# PCB-MicroAudio.net
KiCad netlist of a schematic drawn in EAGLE
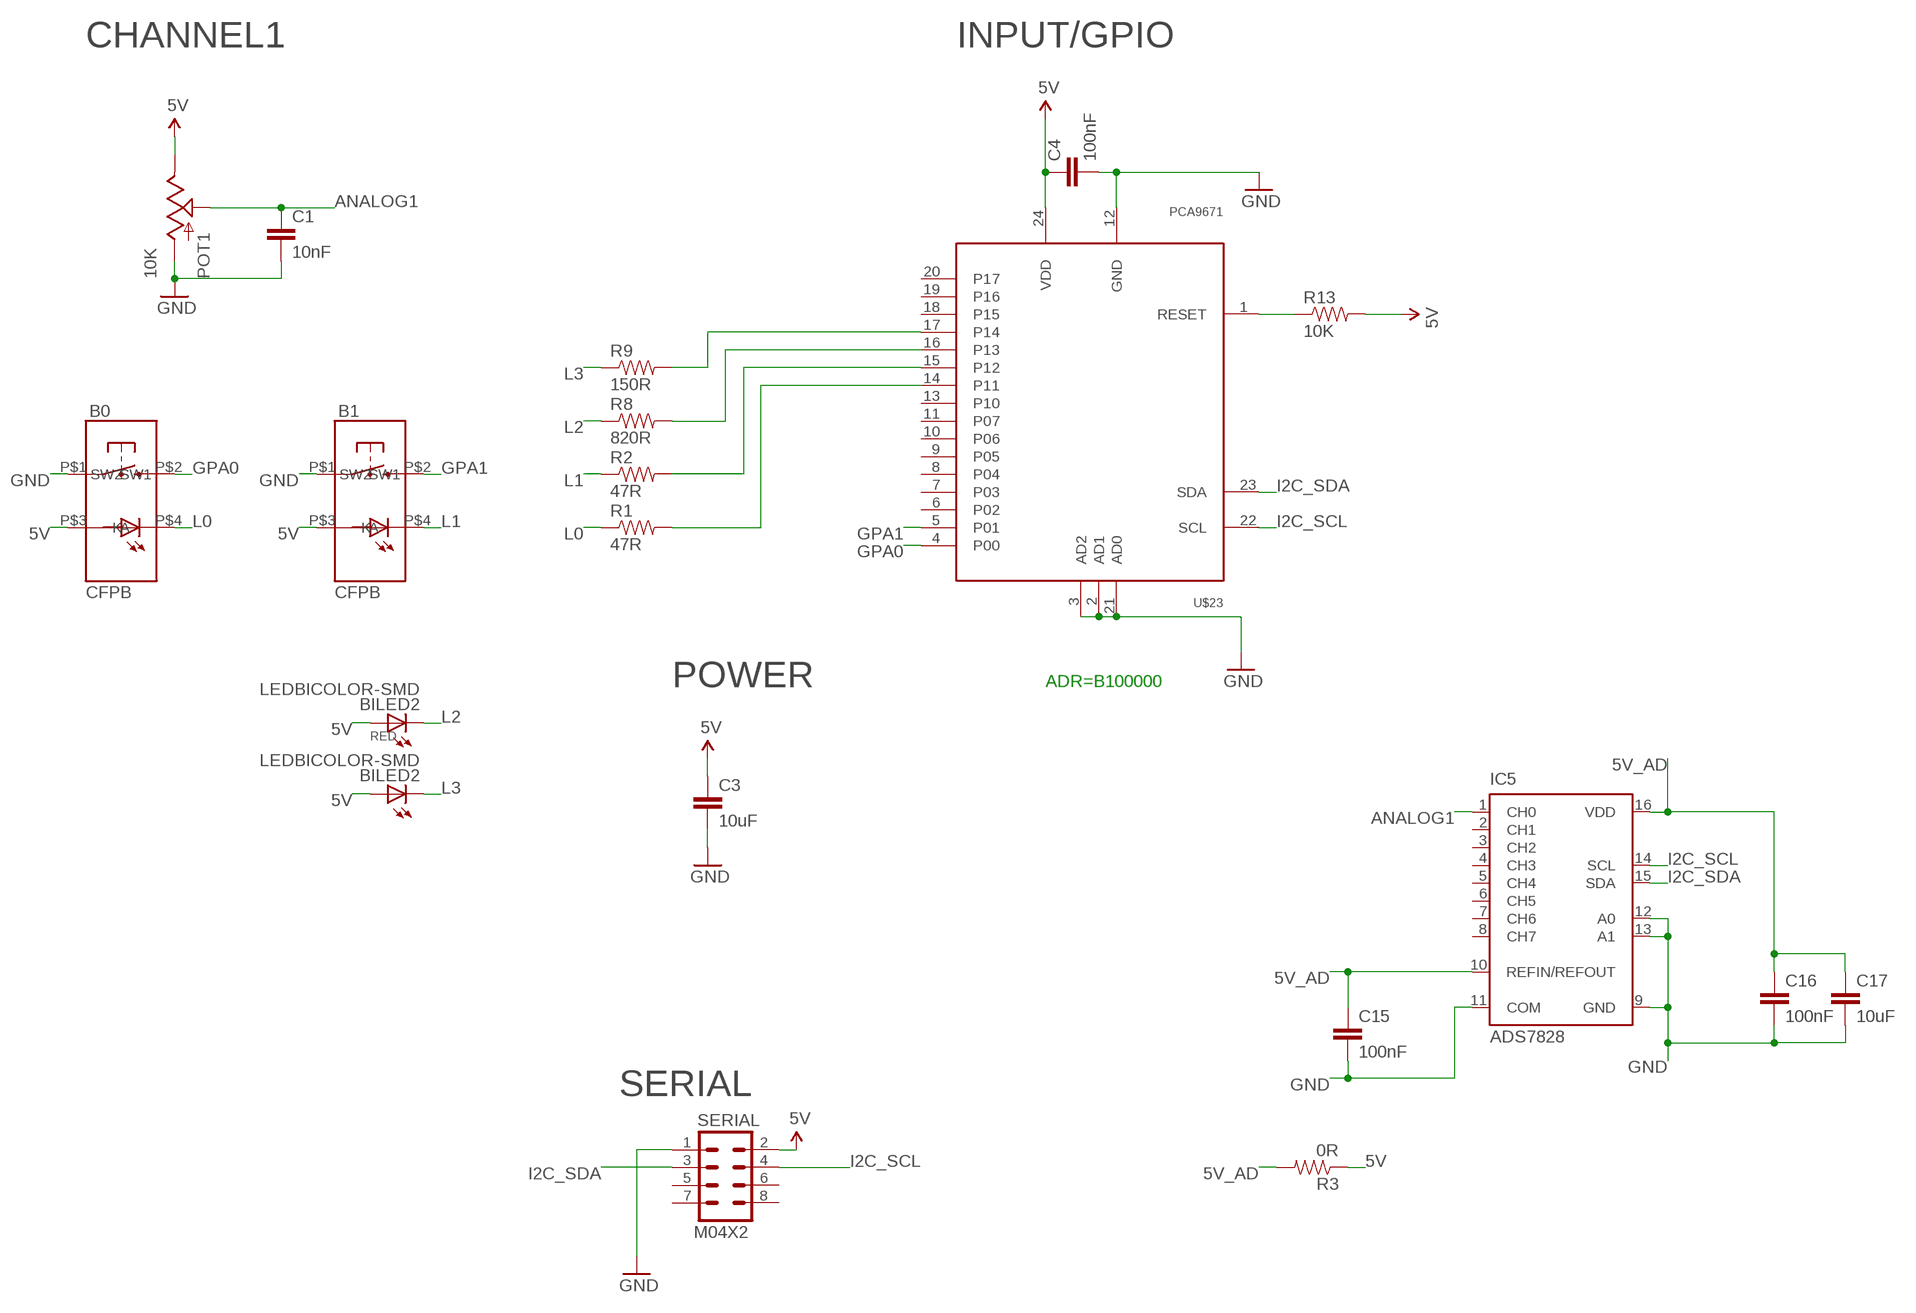
[diagram p0: schematic, sheet 1]

(export (version "E")
  (design (tool "Eeschema 10.0.6"))
  (components
    (comp (ref "B0")
      (value "CFPB")
      (footprint "eagle-import:CFPB-6_9MM")
      (libsource (lib "eagle-import") (part "CFPB"))
    )
    (comp (ref "B1")
      (value "CFPB")
      (footprint "eagle-import:CFPB-6_9MM")
      (libsource (lib "eagle-import") (part "CFPB"))
    )
    (comp (ref "BILED2")
      (value "LEDBICOLOR-SMD")
      (footprint "eagle-import:LEDBICOLOR-SMD")
      (libsource (lib "eagle-import") (part "LEDBICOLOR-SMD"))
    )
    (comp (ref "C1")
      (value "10nF")
      (footprint "eagle-import:0603-CAP")
      (libsource (lib "eagle-import") (part "CAP0603-CAP"))
    )
    (comp (ref "C3")
      (value "10uF")
      (footprint "eagle-import:0805")
      (libsource (lib "eagle-import") (part "CAP0805"))
    )
    (comp (ref "C4")
      (value "100nF")
      (footprint "eagle-import:0603-CAP")
      (libsource (lib "eagle-import") (part "CAP0603-CAP"))
    )
    (comp (ref "C15")
      (value "100nF")
      (footprint "eagle-import:0603-CAP")
      (libsource (lib "eagle-import") (part "CAP0603-CAP"))
    )
    (comp (ref "C16")
      (value "100nF")
      (footprint "eagle-import:0603-CAP")
      (libsource (lib "eagle-import") (part "CAP0603-CAP"))
    )
    (comp (ref "C17")
      (value "10uF")
      (footprint "eagle-import:0805")
      (libsource (lib "eagle-import") (part "CAP0805"))
    )
    (comp (ref "IC5")
      (value "ADS7828")
      (footprint "eagle-import:TSSOP16-PW")
      (fields (field (name "MF") "TEXAS INSTRUMENTS") (field (name "MPN") "ADS7828E/250"))
      (libsource (lib "eagle-import") (part "ADS7828"))
    )
    (comp (ref "POT1")
      (value "10K")
      (footprint "eagle-import:ALPS_POT")
      (libsource (lib "eagle-import") (part "POT"))
    )
    (comp (ref "R1")
      (value "47R")
      (footprint "eagle-import:0603-RES")
      (libsource (lib "eagle-import") (part "RESISTOR0603-RES"))
    )
    (comp (ref "R2")
      (value "47R")
      (footprint "eagle-import:0603-RES")
      (libsource (lib "eagle-import") (part "RESISTOR0603-RES"))
    )
    (comp (ref "R3")
      (value "0R")
      (footprint "eagle-import:0603-RES")
      (libsource (lib "eagle-import") (part "RESISTOR0603-RES"))
    )
    (comp (ref "R8")
      (value "820R")
      (footprint "eagle-import:0603-RES")
      (libsource (lib "eagle-import") (part "RESISTOR0603-RES"))
    )
    (comp (ref "R9")
      (value "150R")
      (footprint "eagle-import:0603-RES")
      (libsource (lib "eagle-import") (part "RESISTOR0603-RES"))
    )
    (comp (ref "R13")
      (value "10K")
      (footprint "eagle-import:0603-RES")
      (libsource (lib "eagle-import") (part "RESISTOR0603-RES"))
    )
    (comp (ref "SERIAL")
      (value "M04X2")
      (footprint "eagle-import:2X4")
      (libsource (lib "eagle-import") (part "M04X2"))
    )
    (comp (ref "U$23")
      (value "PCA9671")
      (footprint "eagle-import:TSSOP24")
      (libsource (lib "eagle-import") (part "PCA9671"))
    )
  )
  (nets
    (net (code "1") (name "5V") (class "Default")
      (node (ref "B0") (pin "P$3") (pinfunction "A_P$3") (pintype "bidirectional"))
      (node (ref "B1") (pin "P$3") (pinfunction "A_P$3") (pintype "bidirectional"))
      (node (ref "BILED2") (pin "P$1") (pinfunction "A_P$1") (pintype "passive"))
      (node (ref "BILED2") (pin "P$3") (pinfunction "A1_P$3") (pintype "passive"))
      (node (ref "C3") (pin "1") (pinfunction "1_1") (pintype "passive"))
      (node (ref "C4") (pin "1") (pinfunction "1_1") (pintype "passive"))
      (node (ref "POT1") (pin "P$1") (pinfunction "E_P$1") (pintype "passive"))
      (node (ref "R13") (pin "2") (pinfunction "2_2") (pintype "passive"))
      (node (ref "R3") (pin "1") (pinfunction "1_1") (pintype "passive"))
      (node (ref "SERIAL") (pin "2") (pinfunction "2_2") (pintype "passive"))
      (node (ref "U$23") (pin "24") (pinfunction "VDD_24") (pintype "power_in"))
    )
    (net (code "2") (name "5V_AD") (class "Default")
      (node (ref "C15") (pin "1") (pinfunction "1_1") (pintype "passive"))
      (node (ref "C16") (pin "1") (pinfunction "1_1") (pintype "passive"))
      (node (ref "C17") (pin "1") (pinfunction "1_1") (pintype "passive"))
      (node (ref "IC5") (pin "10") (pinfunction "REFIN/REFOUT_10") (pintype "passive"))
      (node (ref "IC5") (pin "16") (pinfunction "VDD_16") (pintype "power_in"))
      (node (ref "R3") (pin "2") (pinfunction "2_2") (pintype "passive"))
    )
    (net (code "3") (name "ANALOG1") (class "Default")
      (node (ref "C1") (pin "1") (pinfunction "1_1") (pintype "passive"))
      (node (ref "IC5") (pin "1") (pinfunction "CH0_1") (pintype "input"))
      (node (ref "POT1") (pin "P$2") (pinfunction "S_P$2") (pintype "passive"))
    )
    (net (code "4") (name "GND") (class "Default")
      (node (ref "B0") (pin "P$1") (pinfunction "SW1_P$1") (pintype "bidirectional"))
      (node (ref "B1") (pin "P$1") (pinfunction "SW1_P$1") (pintype "bidirectional"))
      (node (ref "C1") (pin "2") (pinfunction "2_2") (pintype "passive"))
      (node (ref "C15") (pin "2") (pinfunction "2_2") (pintype "passive"))
      (node (ref "C16") (pin "2") (pinfunction "2_2") (pintype "passive"))
      (node (ref "C17") (pin "2") (pinfunction "2_2") (pintype "passive"))
      (node (ref "C3") (pin "2") (pinfunction "2_2") (pintype "passive"))
      (node (ref "C4") (pin "2") (pinfunction "2_2") (pintype "passive"))
      (node (ref "IC5") (pin "11") (pinfunction "COM_11") (pintype "input"))
      (node (ref "IC5") (pin "12") (pinfunction "A0_12") (pintype "input"))
      (node (ref "IC5") (pin "13") (pinfunction "A1_13") (pintype "input"))
      (node (ref "IC5") (pin "9") (pinfunction "GND_9") (pintype "power_in"))
      (node (ref "POT1") (pin "P$3") (pinfunction "A_P$3") (pintype "passive"))
      (node (ref "SERIAL") (pin "1") (pinfunction "1_1") (pintype "passive"))
      (node (ref "U$23") (pin "12") (pinfunction "GND_12") (pintype "power_in"))
      (node (ref "U$23") (pin "2") (pinfunction "AD1_2") (pintype "input"))
      (node (ref "U$23") (pin "21") (pinfunction "AD0_21") (pintype "input"))
      (node (ref "U$23") (pin "3") (pinfunction "AD2_3") (pintype "input"))
    )
    (net (code "5") (name "GPA0") (class "Default")
      (node (ref "B0") (pin "P$2") (pinfunction "SW2_P$2") (pintype "bidirectional"))
      (node (ref "U$23") (pin "4") (pinfunction "P00_4") (pintype "output"))
    )
    (net (code "6") (name "GPA1") (class "Default")
      (node (ref "B1") (pin "P$2") (pinfunction "SW2_P$2") (pintype "bidirectional"))
      (node (ref "U$23") (pin "5") (pinfunction "P01_5") (pintype "output"))
    )
    (net (code "7") (name "I2C_SCL") (class "Default")
      (node (ref "IC5") (pin "14") (pinfunction "SCL_14") (pintype "input"))
      (node (ref "SERIAL") (pin "4") (pinfunction "4_4") (pintype "passive"))
      (node (ref "U$23") (pin "22") (pinfunction "SCL_22") (pintype "input"))
    )
    (net (code "8") (name "I2C_SDA") (class "Default")
      (node (ref "IC5") (pin "15") (pinfunction "SDA_15") (pintype "bidirectional"))
      (node (ref "SERIAL") (pin "3") (pinfunction "3_3") (pintype "passive"))
      (node (ref "U$23") (pin "23") (pinfunction "SDA_23") (pintype "input"))
    )
    (net (code "9") (name "L0") (class "Default")
      (node (ref "B0") (pin "P$4") (pinfunction "K_P$4") (pintype "bidirectional"))
      (node (ref "R1") (pin "1") (pinfunction "1_1") (pintype "passive"))
    )
    (net (code "10") (name "L1") (class "Default")
      (node (ref "B1") (pin "P$4") (pinfunction "K_P$4") (pintype "bidirectional"))
      (node (ref "R2") (pin "1") (pinfunction "1_1") (pintype "passive"))
    )
    (net (code "11") (name "L2") (class "Default")
      (node (ref "BILED2") (pin "P$2") (pinfunction "C_P$2") (pintype "passive"))
      (node (ref "R8") (pin "1") (pinfunction "1_1") (pintype "passive"))
    )
    (net (code "12") (name "L3") (class "Default")
      (node (ref "BILED2") (pin "P$4") (pinfunction "C1_P$4") (pintype "passive"))
      (node (ref "R9") (pin "1") (pinfunction "1_1") (pintype "passive"))
    )
    (net (code "13") (name "Net-(U$23-P11)") (class "Default")
      (node (ref "R1") (pin "2") (pinfunction "2_2") (pintype "passive"))
      (node (ref "U$23") (pin "14") (pinfunction "P11_14") (pintype "output"))
    )
    (net (code "14") (name "Net-(U$23-P12)") (class "Default")
      (node (ref "R2") (pin "2") (pinfunction "2_2") (pintype "passive"))
      (node (ref "U$23") (pin "15") (pinfunction "P12_15") (pintype "output"))
    )
    (net (code "15") (name "Net-(U$23-P13)") (class "Default")
      (node (ref "R8") (pin "2") (pinfunction "2_2") (pintype "passive"))
      (node (ref "U$23") (pin "16") (pinfunction "P13_16") (pintype "output"))
    )
    (net (code "16") (name "Net-(U$23-P14)") (class "Default")
      (node (ref "R9") (pin "2") (pinfunction "2_2") (pintype "passive"))
      (node (ref "U$23") (pin "17") (pinfunction "P14_17") (pintype "output"))
    )
    (net (code "17") (name "Net-(U$23-RESET)") (class "Default")
      (node (ref "R13") (pin "1") (pinfunction "1_1") (pintype "passive"))
      (node (ref "U$23") (pin "1") (pinfunction "RESET_1") (pintype "input"))
    )
    (net (code "18") (name "unconnected-(IC5-CH1-Pad2)") (class "Default")
      (node (ref "IC5") (pin "2") (pinfunction "CH1_2") (pintype "input"))
    )
    (net (code "19") (name "unconnected-(IC5-CH2-Pad3)") (class "Default")
      (node (ref "IC5") (pin "3") (pinfunction "CH2_3") (pintype "input"))
    )
    (net (code "20") (name "unconnected-(IC5-CH3-Pad4)") (class "Default")
      (node (ref "IC5") (pin "4") (pinfunction "CH3_4") (pintype "input"))
    )
    (net (code "21") (name "unconnected-(IC5-CH4-Pad5)") (class "Default")
      (node (ref "IC5") (pin "5") (pinfunction "CH4_5") (pintype "input"))
    )
    (net (code "22") (name "unconnected-(IC5-CH5-Pad6)") (class "Default")
      (node (ref "IC5") (pin "6") (pinfunction "CH5_6") (pintype "input"))
    )
    (net (code "23") (name "unconnected-(IC5-CH6-Pad7)") (class "Default")
      (node (ref "IC5") (pin "7") (pinfunction "CH6_7") (pintype "input"))
    )
    (net (code "24") (name "unconnected-(IC5-CH7-Pad8)") (class "Default")
      (node (ref "IC5") (pin "8") (pinfunction "CH7_8") (pintype "input"))
    )
    (net (code "25") (name "unconnected-(SERIAL-Pad5)") (class "Default")
      (node (ref "SERIAL") (pin "5") (pinfunction "5_5") (pintype "passive"))
    )
    (net (code "26") (name "unconnected-(SERIAL-Pad6)") (class "Default")
      (node (ref "SERIAL") (pin "6") (pinfunction "6_6") (pintype "passive"))
    )
    (net (code "27") (name "unconnected-(SERIAL-Pad7)") (class "Default")
      (node (ref "SERIAL") (pin "7") (pinfunction "7_7") (pintype "passive"))
    )
    (net (code "28") (name "unconnected-(SERIAL-Pad8)") (class "Default")
      (node (ref "SERIAL") (pin "8") (pinfunction "8_8") (pintype "passive"))
    )
    (net (code "29") (name "unconnected-(U$23-P02-Pad6)") (class "Default")
      (node (ref "U$23") (pin "6") (pinfunction "P02_6") (pintype "output"))
    )
    (net (code "30") (name "unconnected-(U$23-P03-Pad7)") (class "Default")
      (node (ref "U$23") (pin "7") (pinfunction "P03_7") (pintype "output"))
    )
    (net (code "31") (name "unconnected-(U$23-P04-Pad8)") (class "Default")
      (node (ref "U$23") (pin "8") (pinfunction "P04_8") (pintype "output"))
    )
    (net (code "32") (name "unconnected-(U$23-P05-Pad9)") (class "Default")
      (node (ref "U$23") (pin "9") (pinfunction "P05_9") (pintype "output"))
    )
    (net (code "33") (name "unconnected-(U$23-P06-Pad10)") (class "Default")
      (node (ref "U$23") (pin "10") (pinfunction "P06_10") (pintype "output"))
    )
    (net (code "34") (name "unconnected-(U$23-P07-Pad11)") (class "Default")
      (node (ref "U$23") (pin "11") (pinfunction "P07_11") (pintype "output"))
    )
    (net (code "35") (name "unconnected-(U$23-P10-Pad13)") (class "Default")
      (node (ref "U$23") (pin "13") (pinfunction "P10_13") (pintype "output"))
    )
    (net (code "36") (name "unconnected-(U$23-P15-Pad18)") (class "Default")
      (node (ref "U$23") (pin "18") (pinfunction "P15_18") (pintype "output"))
    )
    (net (code "37") (name "unconnected-(U$23-P16-Pad19)") (class "Default")
      (node (ref "U$23") (pin "19") (pinfunction "P16_19") (pintype "output"))
    )
    (net (code "38") (name "unconnected-(U$23-P17-Pad20)") (class "Default")
      (node (ref "U$23") (pin "20") (pinfunction "P17_20") (pintype "output"))
    )
  )
)
